# xmas-tree.net
KiCad netlist of a schematic drawn in EAGLE
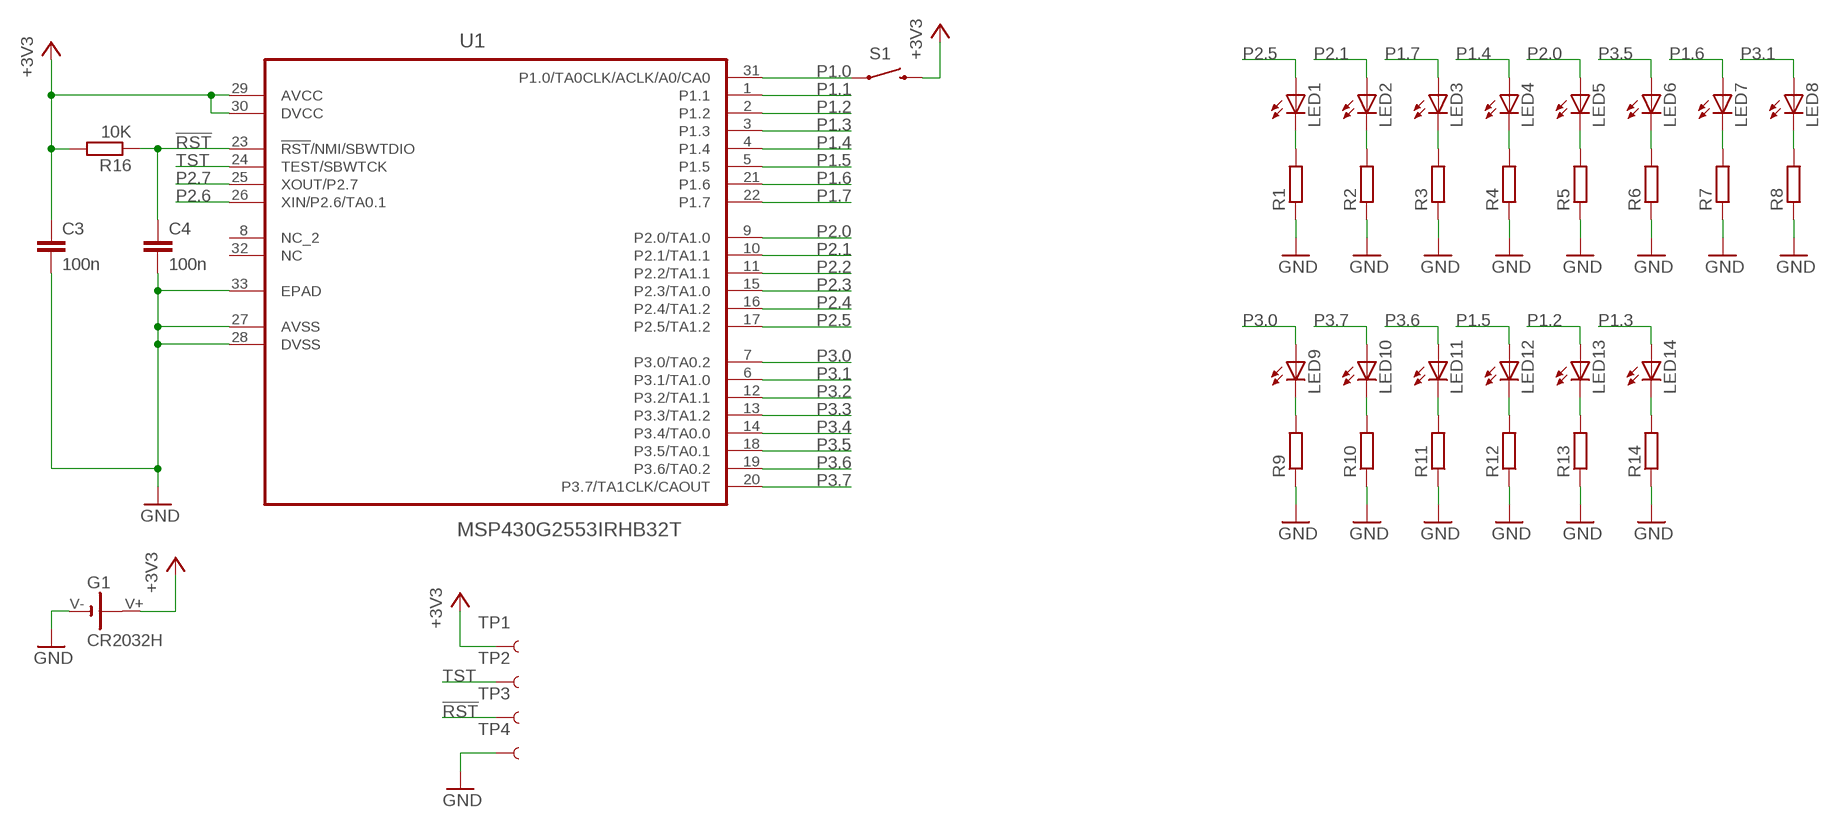
[diagram p0: schematic, sheet 1]

(export (version "E")
  (design (tool "Eeschema 10.0.6"))
  (components
    (comp (ref "C3")
      (value "100n")
      (footprint "eagle-import:C0603")
      (libsource (lib "eagle-import") (part "C-EUC0603"))
    )
    (comp (ref "C4")
      (value "100n")
      (footprint "eagle-import:C0603")
      (libsource (lib "eagle-import") (part "C-EUC0603"))
    )
    (comp (ref "G1")
      (value "CR2032H")
      (footprint "eagle-import:CH7410-2032LF")
      (libsource (lib "eagle-import") (part "CR2032H"))
    )
    (comp (ref "LED1")
      (value "LEDCHIPLED_0603")
      (footprint "eagle-import:CHIPLED_0603")
      (libsource (lib "eagle-import") (part "LEDCHIPLED_0603"))
    )
    (comp (ref "LED2")
      (value "LEDCHIPLED_0603")
      (footprint "eagle-import:CHIPLED_0603")
      (libsource (lib "eagle-import") (part "LEDCHIPLED_0603"))
    )
    (comp (ref "LED3")
      (value "LEDCHIPLED_0603")
      (footprint "eagle-import:CHIPLED_0603")
      (libsource (lib "eagle-import") (part "LEDCHIPLED_0603"))
    )
    (comp (ref "LED4")
      (value "LEDCHIPLED_0603")
      (footprint "eagle-import:CHIPLED_0603")
      (libsource (lib "eagle-import") (part "LEDCHIPLED_0603"))
    )
    (comp (ref "LED5")
      (value "LEDCHIPLED_0603")
      (footprint "eagle-import:CHIPLED_0603")
      (libsource (lib "eagle-import") (part "LEDCHIPLED_0603"))
    )
    (comp (ref "LED6")
      (value "LEDCHIPLED_0603")
      (footprint "eagle-import:CHIPLED_0603")
      (libsource (lib "eagle-import") (part "LEDCHIPLED_0603"))
    )
    (comp (ref "LED7")
      (value "LEDCHIPLED_0603")
      (footprint "eagle-import:CHIPLED_0603")
      (libsource (lib "eagle-import") (part "LEDCHIPLED_0603"))
    )
    (comp (ref "LED8")
      (value "LEDCHIPLED_0603")
      (footprint "eagle-import:CHIPLED_0603")
      (libsource (lib "eagle-import") (part "LEDCHIPLED_0603"))
    )
    (comp (ref "LED9")
      (value "LEDCHIPLED_0603")
      (footprint "eagle-import:CHIPLED_0603")
      (libsource (lib "eagle-import") (part "LEDCHIPLED_0603"))
    )
    (comp (ref "LED10")
      (value "LEDCHIPLED_0603")
      (footprint "eagle-import:CHIPLED_0603")
      (libsource (lib "eagle-import") (part "LEDCHIPLED_0603"))
    )
    (comp (ref "LED11")
      (value "LEDCHIPLED_0603")
      (footprint "eagle-import:CHIPLED_0603")
      (libsource (lib "eagle-import") (part "LEDCHIPLED_0603"))
    )
    (comp (ref "LED12")
      (value "LEDCHIPLED_0603")
      (footprint "eagle-import:CHIPLED_0603")
      (libsource (lib "eagle-import") (part "LEDCHIPLED_0603"))
    )
    (comp (ref "LED13")
      (value "LEDCHIPLED_0603")
      (footprint "eagle-import:CHIPLED_0603")
      (libsource (lib "eagle-import") (part "LEDCHIPLED_0603"))
    )
    (comp (ref "LED14")
      (value "LEDCHIPLED_0603")
      (footprint "eagle-import:CHIPLED_0603")
      (libsource (lib "eagle-import") (part "LEDCHIPLED_0603"))
    )
    (comp (ref "R1")
      (value "R-EU_R0603")
      (footprint "eagle-import:R0603")
      (libsource (lib "eagle-import") (part "R-EU_R0603"))
    )
    (comp (ref "R2")
      (value "R-EU_R0603")
      (footprint "eagle-import:R0603")
      (libsource (lib "eagle-import") (part "R-EU_R0603"))
    )
    (comp (ref "R3")
      (value "R-EU_R0603")
      (footprint "eagle-import:R0603")
      (libsource (lib "eagle-import") (part "R-EU_R0603"))
    )
    (comp (ref "R4")
      (value "R-EU_R0603")
      (footprint "eagle-import:R0603")
      (libsource (lib "eagle-import") (part "R-EU_R0603"))
    )
    (comp (ref "R5")
      (value "R-EU_R0603")
      (footprint "eagle-import:R0603")
      (libsource (lib "eagle-import") (part "R-EU_R0603"))
    )
    (comp (ref "R6")
      (value "R-EU_R0603")
      (footprint "eagle-import:R0603")
      (libsource (lib "eagle-import") (part "R-EU_R0603"))
    )
    (comp (ref "R7")
      (value "R-EU_R0603")
      (footprint "eagle-import:R0603")
      (libsource (lib "eagle-import") (part "R-EU_R0603"))
    )
    (comp (ref "R8")
      (value "R-EU_R0603")
      (footprint "eagle-import:R0603")
      (libsource (lib "eagle-import") (part "R-EU_R0603"))
    )
    (comp (ref "R9")
      (value "R-EU_R0603")
      (footprint "eagle-import:R0603")
      (libsource (lib "eagle-import") (part "R-EU_R0603"))
    )
    (comp (ref "R10")
      (value "R-EU_R0603")
      (footprint "eagle-import:R0603")
      (libsource (lib "eagle-import") (part "R-EU_R0603"))
    )
    (comp (ref "R11")
      (value "R-EU_R0603")
      (footprint "eagle-import:R0603")
      (libsource (lib "eagle-import") (part "R-EU_R0603"))
    )
    (comp (ref "R12")
      (value "R-EU_R0603")
      (footprint "eagle-import:R0603")
      (libsource (lib "eagle-import") (part "R-EU_R0603"))
    )
    (comp (ref "R13")
      (value "R-EU_R0603")
      (footprint "eagle-import:R0603")
      (libsource (lib "eagle-import") (part "R-EU_R0603"))
    )
    (comp (ref "R14")
      (value "R-EU_R0603")
      (footprint "eagle-import:R0603")
      (libsource (lib "eagle-import") (part "R-EU_R0603"))
    )
    (comp (ref "R16")
      (value "10K")
      (footprint "eagle-import:R0603")
      (libsource (lib "eagle-import") (part "R-EU_R0603"))
    )
    (comp (ref "S1")
      (value "SWITCH-MOMENTARY-2SMD-REDUNDANT")
      (footprint "eagle-import:TACTILE-SWITCH-SMD")
      (libsource (lib "eagle-import") (part "SWITCH-MOMENTARY-2SMD-REDUNDANT"))
    )
    (comp (ref "TP1")
      (value "+3V3")
      (footprint "eagle-import:PAD.03X.05")
      (libsource (lib "eagle-import") (part "TEST-POINT3X5"))
    )
    (comp (ref "TP2")
      (value "TST")
      (footprint "eagle-import:PAD.03X.05")
      (libsource (lib "eagle-import") (part "TEST-POINT3X5"))
    )
    (comp (ref "TP3")
      (value "RST")
      (footprint "eagle-import:PAD.03X.05")
      (libsource (lib "eagle-import") (part "TEST-POINT3X5"))
    )
    (comp (ref "TP4")
      (value "GND")
      (footprint "eagle-import:PAD.03X.05")
      (libsource (lib "eagle-import") (part "TEST-POINT3X5"))
    )
    (comp (ref "U1")
      (value "MSP430G2553IRHB32T")
      (footprint "eagle-import:QFN50P500X500X100-33N")
      (libsource (lib "eagle-import") (part "MSP430G2553IRHB32T"))
    )
  )
  (nets
    (net (code "1") (name "+3V3") (class "Default")
      (node (ref "C3") (pin "1") (pinfunction "1_1") (pintype "passive"))
      (node (ref "G1") (pin "V+") (pinfunction "V+_V+") (pintype "passive"))
      (node (ref "R16") (pin "2") (pinfunction "2_2") (pintype "passive"))
      (node (ref "S1") (pin "3") (pinfunction "2_3") (pintype "passive"))
      (node (ref "S1") (pin "4") (pinfunction "2_4") (pintype "passive"))
      (node (ref "TP1") (pin "P$1") (pinfunction "1_P$1") (pintype "bidirectional"))
      (node (ref "U1") (pin "29") (pinfunction "AVCC_29") (pintype "power_in"))
      (node (ref "U1") (pin "30") (pinfunction "DVCC_30") (pintype "power_in"))
    )
    (net (code "2") (name "/P1.0") (class "Default")
      (node (ref "S1") (pin "1") (pinfunction "1_1") (pintype "passive"))
      (node (ref "S1") (pin "2") (pinfunction "1_2") (pintype "passive"))
      (node (ref "U1") (pin "31") (pinfunction "P1.0/TA0CLK/ACLK/A0/CA0_31") (pintype "bidirectional"))
    )
    (net (code "3") (name "/P1.1") (class "Default")
      (node (ref "U1") (pin "1") (pinfunction "P1.1_1") (pintype "bidirectional"))
    )
    (net (code "4") (name "/P1.2") (class "Default")
      (node (ref "LED13") (pin "A") (pinfunction "A_A") (pintype "passive"))
      (node (ref "U1") (pin "2") (pinfunction "P1.2_2") (pintype "bidirectional"))
    )
    (net (code "5") (name "/P1.3") (class "Default")
      (node (ref "LED14") (pin "A") (pinfunction "A_A") (pintype "passive"))
      (node (ref "U1") (pin "3") (pinfunction "P1.3_3") (pintype "bidirectional"))
    )
    (net (code "6") (name "/P1.4") (class "Default")
      (node (ref "LED4") (pin "A") (pinfunction "A_A") (pintype "passive"))
      (node (ref "U1") (pin "4") (pinfunction "P1.4_4") (pintype "bidirectional"))
    )
    (net (code "7") (name "/P1.5") (class "Default")
      (node (ref "LED12") (pin "A") (pinfunction "A_A") (pintype "passive"))
      (node (ref "U1") (pin "5") (pinfunction "P1.5_5") (pintype "bidirectional"))
    )
    (net (code "8") (name "/P1.6") (class "Default")
      (node (ref "LED7") (pin "A") (pinfunction "A_A") (pintype "passive"))
      (node (ref "U1") (pin "21") (pinfunction "P1.6_21") (pintype "bidirectional"))
    )
    (net (code "9") (name "/P1.7") (class "Default")
      (node (ref "LED3") (pin "A") (pinfunction "A_A") (pintype "passive"))
      (node (ref "U1") (pin "22") (pinfunction "P1.7_22") (pintype "bidirectional"))
    )
    (net (code "10") (name "/P2.0") (class "Default")
      (node (ref "LED5") (pin "A") (pinfunction "A_A") (pintype "passive"))
      (node (ref "U1") (pin "9") (pinfunction "P2.0/TA1.0_9") (pintype "bidirectional"))
    )
    (net (code "11") (name "/P2.1") (class "Default")
      (node (ref "LED2") (pin "A") (pinfunction "A_A") (pintype "passive"))
      (node (ref "U1") (pin "10") (pinfunction "P2.1/TA1.1_10") (pintype "bidirectional"))
    )
    (net (code "12") (name "/P2.2") (class "Default")
      (node (ref "U1") (pin "11") (pinfunction "P2.2/TA1.1_11") (pintype "bidirectional"))
    )
    (net (code "13") (name "/P2.3") (class "Default")
      (node (ref "U1") (pin "15") (pinfunction "P2.3/TA1.0_15") (pintype "bidirectional"))
    )
    (net (code "14") (name "/P2.4") (class "Default")
      (node (ref "U1") (pin "16") (pinfunction "P2.4/TA1.2_16") (pintype "bidirectional"))
    )
    (net (code "15") (name "/P2.5") (class "Default")
      (node (ref "LED1") (pin "A") (pinfunction "A_A") (pintype "passive"))
      (node (ref "U1") (pin "17") (pinfunction "P2.5/TA1.2_17") (pintype "bidirectional"))
    )
    (net (code "16") (name "/P2.6") (class "Default")
      (node (ref "U1") (pin "26") (pinfunction "XIN/P2.6/TA0.1_26") (pintype "bidirectional"))
    )
    (net (code "17") (name "/P2.7") (class "Default")
      (node (ref "U1") (pin "25") (pinfunction "XOUT/P2.7_25") (pintype "bidirectional"))
    )
    (net (code "18") (name "/P3.0") (class "Default")
      (node (ref "LED9") (pin "A") (pinfunction "A_A") (pintype "passive"))
      (node (ref "U1") (pin "7") (pinfunction "P3.0/TA0.2_7") (pintype "bidirectional"))
    )
    (net (code "19") (name "/P3.1") (class "Default")
      (node (ref "LED8") (pin "A") (pinfunction "A_A") (pintype "passive"))
      (node (ref "U1") (pin "6") (pinfunction "P3.1/TA1.0_6") (pintype "bidirectional"))
    )
    (net (code "20") (name "/P3.2") (class "Default")
      (node (ref "U1") (pin "12") (pinfunction "P3.2/TA1.1_12") (pintype "bidirectional"))
    )
    (net (code "21") (name "/P3.3") (class "Default")
      (node (ref "U1") (pin "13") (pinfunction "P3.3/TA1.2_13") (pintype "bidirectional"))
    )
    (net (code "22") (name "/P3.4") (class "Default")
      (node (ref "U1") (pin "14") (pinfunction "P3.4/TA0.0_14") (pintype "bidirectional"))
    )
    (net (code "23") (name "/P3.5") (class "Default")
      (node (ref "LED6") (pin "A") (pinfunction "A_A") (pintype "passive"))
      (node (ref "U1") (pin "18") (pinfunction "P3.5/TA0.1_18") (pintype "bidirectional"))
    )
    (net (code "24") (name "/P3.6") (class "Default")
      (node (ref "LED11") (pin "A") (pinfunction "A_A") (pintype "passive"))
      (node (ref "U1") (pin "19") (pinfunction "P3.6/TA0.2_19") (pintype "bidirectional"))
    )
    (net (code "25") (name "/P3.7") (class "Default")
      (node (ref "LED10") (pin "A") (pinfunction "A_A") (pintype "passive"))
      (node (ref "U1") (pin "20") (pinfunction "P3.7/TA1CLK/CAOUT_20") (pintype "bidirectional"))
    )
    (net (code "26") (name "/TST") (class "Default")
      (node (ref "TP2") (pin "P$1") (pinfunction "1_P$1") (pintype "bidirectional"))
      (node (ref "U1") (pin "24") (pinfunction "TEST/SBWTCK_24") (pintype "bidirectional"))
    )
    (net (code "27") (name "/~{RST}") (class "Default")
      (node (ref "C4") (pin "1") (pinfunction "1_1") (pintype "passive"))
      (node (ref "R16") (pin "1") (pinfunction "1_1") (pintype "passive"))
      (node (ref "TP3") (pin "P$1") (pinfunction "1_P$1") (pintype "bidirectional"))
      (node (ref "U1") (pin "23") (pinfunction "~{RST}/NMI/SBWTDIO_23") (pintype "bidirectional"))
    )
    (net (code "28") (name "GND") (class "Default")
      (node (ref "C3") (pin "2") (pinfunction "2_2") (pintype "passive"))
      (node (ref "C4") (pin "2") (pinfunction "2_2") (pintype "passive"))
      (node (ref "G1") (pin "V-") (pinfunction "V-_V-") (pintype "passive"))
      (node (ref "R1") (pin "1") (pinfunction "1_1") (pintype "passive"))
      (node (ref "R10") (pin "1") (pinfunction "1_1") (pintype "passive"))
      (node (ref "R11") (pin "1") (pinfunction "1_1") (pintype "passive"))
      (node (ref "R12") (pin "1") (pinfunction "1_1") (pintype "passive"))
      (node (ref "R13") (pin "1") (pinfunction "1_1") (pintype "passive"))
      (node (ref "R14") (pin "1") (pinfunction "1_1") (pintype "passive"))
      (node (ref "R2") (pin "1") (pinfunction "1_1") (pintype "passive"))
      (node (ref "R3") (pin "1") (pinfunction "1_1") (pintype "passive"))
      (node (ref "R4") (pin "1") (pinfunction "1_1") (pintype "passive"))
      (node (ref "R5") (pin "1") (pinfunction "1_1") (pintype "passive"))
      (node (ref "R6") (pin "1") (pinfunction "1_1") (pintype "passive"))
      (node (ref "R7") (pin "1") (pinfunction "1_1") (pintype "passive"))
      (node (ref "R8") (pin "1") (pinfunction "1_1") (pintype "passive"))
      (node (ref "R9") (pin "1") (pinfunction "1_1") (pintype "passive"))
      (node (ref "TP4") (pin "P$1") (pinfunction "1_P$1") (pintype "bidirectional"))
      (node (ref "U1") (pin "27") (pinfunction "AVSS_27") (pintype "passive"))
      (node (ref "U1") (pin "28") (pinfunction "DVSS_28") (pintype "passive"))
      (node (ref "U1") (pin "33") (pinfunction "EPAD_33") (pintype "passive"))
    )
    (net (code "29") (name "Net-(LED1-PadC)") (class "Default")
      (node (ref "LED1") (pin "C") (pinfunction "C_C") (pintype "passive"))
      (node (ref "R1") (pin "2") (pinfunction "2_2") (pintype "passive"))
    )
    (net (code "30") (name "Net-(LED2-PadC)") (class "Default")
      (node (ref "LED2") (pin "C") (pinfunction "C_C") (pintype "passive"))
      (node (ref "R2") (pin "2") (pinfunction "2_2") (pintype "passive"))
    )
    (net (code "31") (name "Net-(LED3-PadC)") (class "Default")
      (node (ref "LED3") (pin "C") (pinfunction "C_C") (pintype "passive"))
      (node (ref "R3") (pin "2") (pinfunction "2_2") (pintype "passive"))
    )
    (net (code "32") (name "Net-(LED4-PadC)") (class "Default")
      (node (ref "LED4") (pin "C") (pinfunction "C_C") (pintype "passive"))
      (node (ref "R4") (pin "2") (pinfunction "2_2") (pintype "passive"))
    )
    (net (code "33") (name "Net-(LED5-PadC)") (class "Default")
      (node (ref "LED5") (pin "C") (pinfunction "C_C") (pintype "passive"))
      (node (ref "R5") (pin "2") (pinfunction "2_2") (pintype "passive"))
    )
    (net (code "34") (name "Net-(LED6-PadC)") (class "Default")
      (node (ref "LED6") (pin "C") (pinfunction "C_C") (pintype "passive"))
      (node (ref "R6") (pin "2") (pinfunction "2_2") (pintype "passive"))
    )
    (net (code "35") (name "Net-(LED7-PadC)") (class "Default")
      (node (ref "LED7") (pin "C") (pinfunction "C_C") (pintype "passive"))
      (node (ref "R7") (pin "2") (pinfunction "2_2") (pintype "passive"))
    )
    (net (code "36") (name "Net-(LED8-PadC)") (class "Default")
      (node (ref "LED8") (pin "C") (pinfunction "C_C") (pintype "passive"))
      (node (ref "R8") (pin "2") (pinfunction "2_2") (pintype "passive"))
    )
    (net (code "37") (name "Net-(LED9-PadC)") (class "Default")
      (node (ref "LED9") (pin "C") (pinfunction "C_C") (pintype "passive"))
      (node (ref "R9") (pin "2") (pinfunction "2_2") (pintype "passive"))
    )
    (net (code "38") (name "Net-(LED10-PadC)") (class "Default")
      (node (ref "LED10") (pin "C") (pinfunction "C_C") (pintype "passive"))
      (node (ref "R10") (pin "2") (pinfunction "2_2") (pintype "passive"))
    )
    (net (code "39") (name "Net-(LED11-PadC)") (class "Default")
      (node (ref "LED11") (pin "C") (pinfunction "C_C") (pintype "passive"))
      (node (ref "R11") (pin "2") (pinfunction "2_2") (pintype "passive"))
    )
    (net (code "40") (name "Net-(LED12-PadC)") (class "Default")
      (node (ref "LED12") (pin "C") (pinfunction "C_C") (pintype "passive"))
      (node (ref "R12") (pin "2") (pinfunction "2_2") (pintype "passive"))
    )
    (net (code "41") (name "Net-(LED13-PadC)") (class "Default")
      (node (ref "LED13") (pin "C") (pinfunction "C_C") (pintype "passive"))
      (node (ref "R13") (pin "2") (pinfunction "2_2") (pintype "passive"))
    )
    (net (code "42") (name "Net-(LED14-PadC)") (class "Default")
      (node (ref "LED14") (pin "C") (pinfunction "C_C") (pintype "passive"))
      (node (ref "R14") (pin "2") (pinfunction "2_2") (pintype "passive"))
    )
    (net (code "43") (name "unconnected-(U1-NC-Pad32)") (class "Default")
      (node (ref "U1") (pin "32") (pinfunction "NC_32") (pintype "no_connect"))
    )
    (net (code "44") (name "unconnected-(U1-NC_2-Pad8)") (class "Default")
      (node (ref "U1") (pin "8") (pinfunction "NC_2_8") (pintype "no_connect"))
    )
  )
)
